# 0-TempSensor.net
KiCad netlist of a schematic drawn in Altium Designer
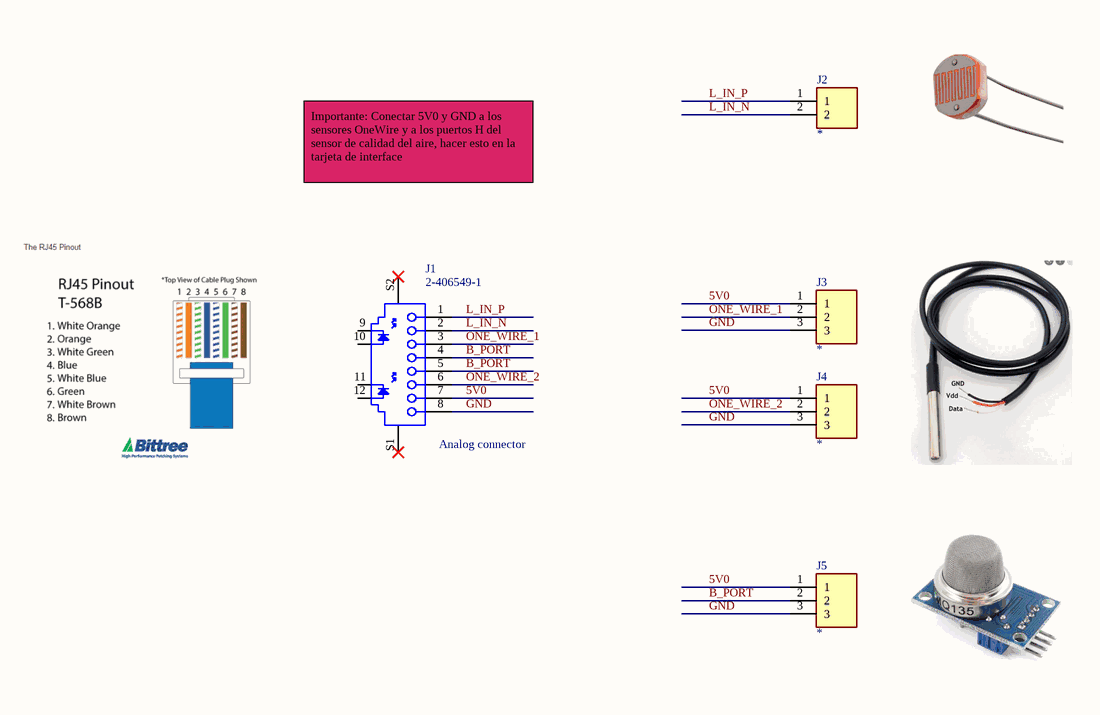
[diagram p0: 0-TempSensor.SchDoc]

(export (version "E")
  (design (tool "Eeschema 10.0.6"))
  (components
    (comp (ref "J1")
      (value "2-406549-1")
      (footprint "TECO-2-406549-1_V")
      (description "RJ45 Connector, Pitch 1.016 mm, 8 Position, Height 14.22 mm, Tail Length 3.18 mm, RoHS, Tray")
      (fields (field (name "MANUFACTURER") "TE Connectivity"))
      (libsource (lib "Altium Content Vault") (part "RJ45-12-2SHLD_A"))
    )
    (comp (ref "J2")
      (value "282841-2")
      (footprint "TE_282841-2")
      (description "Conn Terminal Block 2 POS 5.08mm Solder ST Thru-Hole 17.5A/Contact")
      (fields (field (name "MF") "TE Connectivity") (field (name "COMMENT_1") "*"))
      (libsource (lib "PTR500-2") (part "282841-2"))
    )
    (comp (ref "J3")
      (value "282841-3")
      (footprint "TE_282841-3")
      (description "Conn Terminal Block 3 POS 5.08mm Solder ST Thru-Hole 17.5A/Contact")
      (fields
        (field (name "MF") "TE Connectivity")
        (field (name "MP") "282841-2")
        (field (name "COMMENT_1") "*")
      )
      (libsource (lib "PTR500-2") (part "282841-3"))
    )
    (comp (ref "J4")
      (value "282841-3")
      (footprint "TE_282841-3")
      (description "Conn Terminal Block 3 POS 5.08mm Solder ST Thru-Hole 17.5A/Contact")
      (fields
        (field (name "MF") "TE Connectivity")
        (field (name "MP") "282841-2")
        (field (name "COMMENT_1") "*")
      )
      (libsource (lib "PTR500-2") (part "282841-3"))
    )
    (comp (ref "J5")
      (value "282841-3")
      (footprint "TE_282841-3")
      (description "Conn Terminal Block 3 POS 5.08mm Solder ST Thru-Hole 17.5A/Contact")
      (fields
        (field (name "MF") "TE Connectivity")
        (field (name "MP") "282841-2")
        (field (name "COMMENT_1") "*")
      )
      (libsource (lib "PTR500-2") (part "282841-3"))
    )
  )
  (nets
    (net (code "1") (name "/5V0") (class "Default")
      (node (ref "J1") (pin "7") (pinfunction "7_7") (pintype "passive"))
      (node (ref "J3") (pin "1") (pinfunction "1_1") (pintype "passive"))
      (node (ref "J4") (pin "1") (pinfunction "1_1") (pintype "passive"))
      (node (ref "J5") (pin "1") (pinfunction "1_1") (pintype "passive"))
    )
    (net (code "2") (name "/B_PORT") (class "Default")
      (node (ref "J1") (pin "4") (pinfunction "4_4") (pintype "passive"))
      (node (ref "J1") (pin "5") (pinfunction "5_5") (pintype "passive"))
      (node (ref "J5") (pin "2") (pinfunction "2_2") (pintype "passive"))
    )
    (net (code "3") (name "/GND") (class "Default")
      (node (ref "J1") (pin "8") (pinfunction "8_8") (pintype "passive"))
      (node (ref "J3") (pin "3") (pinfunction "3_3") (pintype "passive"))
      (node (ref "J4") (pin "3") (pinfunction "3_3") (pintype "passive"))
      (node (ref "J5") (pin "3") (pinfunction "3_3") (pintype "passive"))
    )
    (net (code "4") (name "/L_IN_N") (class "Default")
      (node (ref "J1") (pin "2") (pinfunction "2_2") (pintype "passive"))
      (node (ref "J2") (pin "2") (pinfunction "2_2") (pintype "passive"))
    )
    (net (code "5") (name "/L_IN_P") (class "Default")
      (node (ref "J1") (pin "1") (pinfunction "1_1") (pintype "passive"))
      (node (ref "J2") (pin "1") (pinfunction "1_1") (pintype "passive"))
    )
    (net (code "6") (name "/ONE_WIRE_1") (class "Default")
      (node (ref "J1") (pin "3") (pinfunction "3_3") (pintype "passive"))
      (node (ref "J3") (pin "2") (pinfunction "2_2") (pintype "passive"))
    )
    (net (code "7") (name "/ONE_WIRE_2") (class "Default")
      (node (ref "J1") (pin "6") (pinfunction "6_6") (pintype "passive"))
      (node (ref "J4") (pin "2") (pinfunction "2_2") (pintype "passive"))
    )
    (net (code "8") (name "unconnected-(J1-Pad9)") (class "Default")
      (node (ref "J1") (pin "9") (pinfunction "9_9") (pintype "passive"))
    )
    (net (code "9") (name "unconnected-(J1-Pad10)") (class "Default")
      (node (ref "J1") (pin "10") (pinfunction "10_10") (pintype "passive"))
    )
    (net (code "10") (name "unconnected-(J1-Pad11)") (class "Default")
      (node (ref "J1") (pin "11") (pinfunction "11_11") (pintype "passive"))
    )
    (net (code "11") (name "unconnected-(J1-Pad12)") (class "Default")
      (node (ref "J1") (pin "12") (pinfunction "12_12") (pintype "passive"))
    )
    (net (code "12") (name "unconnected-(J1-PadS1)") (class "Default")
      (node (ref "J1") (pin "S1") (pinfunction "S1_S1") (pintype "passive+no_connect"))
    )
    (net (code "13") (name "unconnected-(J1-PadS2)") (class "Default")
      (node (ref "J1") (pin "S2") (pinfunction "S2_S2") (pintype "passive+no_connect"))
    )
  )
)
